# Sensor_Glove_ECG-X01.net
KiCad netlist of a schematic drawn in Altium Designer
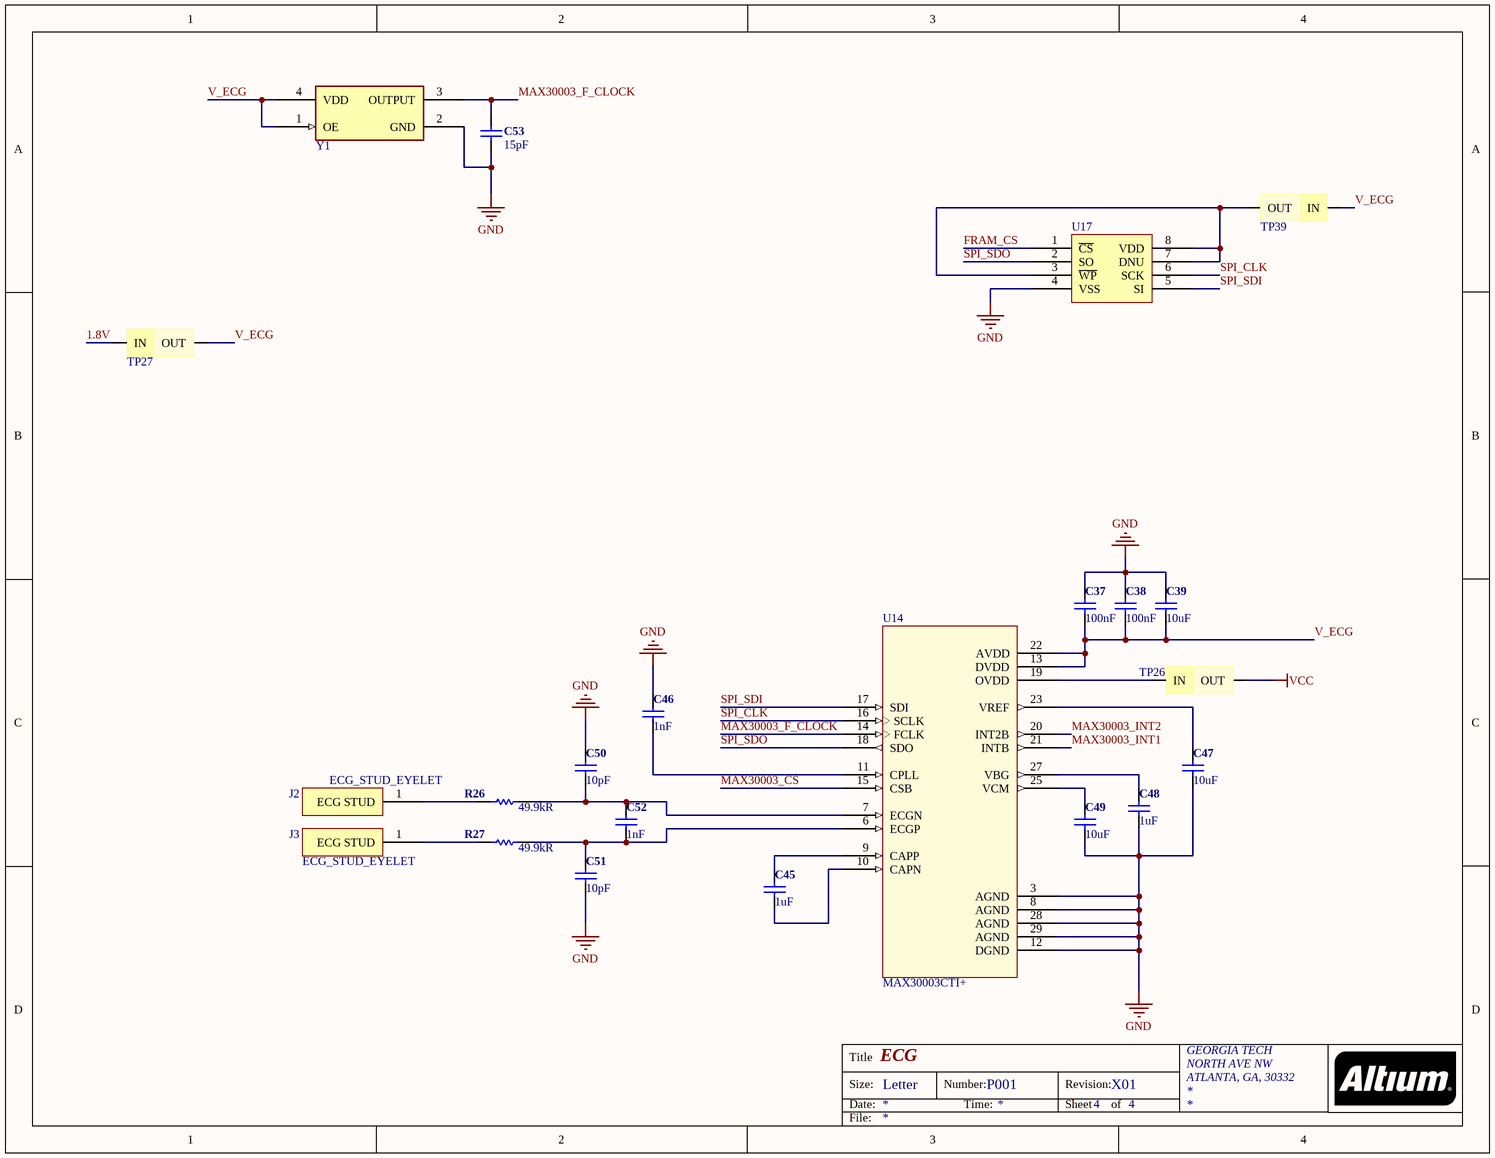
[diagram p0: Sensor_Glove_ECG-X01.SchDoc]

(export (version "E")
  (design (tool "Eeschema 10.0.6"))
  (components
    (comp (ref "C37")
      (value "100nF")
      (footprint "C0603")
      (fields
        (field (name "MANUFACTURER") "Yageo")
        (field (name "MANUFACTURER PART NUMBER") "CC0402ZRY5V8BB104")
        (field (name "TOLERANCE") "80%")
      )
      (libsource (lib "DB-X01") (part "C-0603(1608)"))
    )
    (comp (ref "C38")
      (value "100nF")
      (footprint "C0603")
      (fields
        (field (name "MANUFACTURER") "Yageo")
        (field (name "MANUFACTURER PART NUMBER") "CC0402ZRY5V8BB104")
        (field (name "TOLERANCE") "80%")
      )
      (libsource (lib "DB-X01") (part "C-0603(1608)"))
    )
    (comp (ref "C39")
      (value "10uF")
      (footprint "C0603")
      (fields
        (field (name "MANUFACTURER") "Murata")
        (field (name "MANUFACTURER PART NUMBER") "GRM188R61E106MA73J")
        (field (name "TOLERANCE") "20%")
      )
      (libsource (lib "DB-X01") (part "C-0603(1608)"))
    )
    (comp (ref "C45")
      (value "1uF")
      (footprint "C0402")
      (fields
        (field (name "MANUFACTURER") "Yageo")
        (field (name "MANUFACTURER PART NUMBER") "CC0402MRX5R5BB105")
        (field (name "TOLERANCE") "20%")
      )
      (libsource (lib "DB-X01") (part "C-0402(1005)"))
    )
    (comp (ref "C46")
      (value "1nF")
      (footprint "C0402")
      (description "Ceramic Capacitor, Multilayer, Ceramic, 10V, 5% +Tol, 5% -Tol, C0G, -/+30ppm/Cel TC, 0.001uF, 0402")
      (fields
        (field (name "MANUFACTURER") "KEMET")
        (field (name "MANUFACTURER PART NUMBER") "C0402C102J8GAC7867")
      )
      (libsource (lib "DB-X01") (part "C-0402(1005)"))
    )
    (comp (ref "C47")
      (value "10uF")
      (footprint "C0603")
      (fields
        (field (name "MANUFACTURER") "Murata")
        (field (name "MANUFACTURER PART NUMBER") "GRM188R61E106MA73J")
        (field (name "TOLERANCE") "20%")
      )
      (libsource (lib "DB-X01") (part "C-0603(1608)"))
    )
    (comp (ref "C48")
      (value "1uF")
      (footprint "C0402")
      (fields
        (field (name "MANUFACTURER") "Yageo")
        (field (name "MANUFACTURER PART NUMBER") "CC0402MRX5R5BB105")
        (field (name "TOLERANCE") "20%")
      )
      (libsource (lib "DB-X01") (part "C-0402(1005)"))
    )
    (comp (ref "C49")
      (value "10uF")
      (footprint "C0603")
      (fields
        (field (name "MANUFACTURER") "Murata")
        (field (name "MANUFACTURER PART NUMBER") "GRM188R61E106MA73J")
        (field (name "TOLERANCE") "20%")
      )
      (libsource (lib "DB-X01") (part "C-0603(1608)"))
    )
    (comp (ref "C50")
      (value "10pF")
      (footprint "C0402")
      (fields
        (field (name "MANUFACTURER") "Murata")
        (field (name "MANUFACTURER PART NUMBER") "GJM1555C1H100JB01D")
        (field (name "TOLERANCE") "5%")
      )
      (libsource (lib "DB-X01") (part "C-0402(1005)"))
    )
    (comp (ref "C51")
      (value "10pF")
      (footprint "C0402")
      (fields
        (field (name "MANUFACTURER") "Murata")
        (field (name "MANUFACTURER PART NUMBER") "GJM1555C1H100JB01D")
        (field (name "TOLERANCE") "5%")
      )
      (libsource (lib "DB-X01") (part "C-0402(1005)"))
    )
    (comp (ref "C52")
      (value "1nF")
      (footprint "C0402")
      (description "Ceramic Capacitor, Multilayer, Ceramic, 10V, 5% +Tol, 5% -Tol, C0G, -/+30ppm/Cel TC, 0.001uF, 0402")
      (fields
        (field (name "MANUFACTURER") "KEMET")
        (field (name "MANUFACTURER PART NUMBER") "C0402C102J8GAC7867")
      )
      (libsource (lib "DB-X01") (part "C-0402(1005)"))
    )
    (comp (ref "C53")
      (value "15pF")
      (footprint "C0402")
      (fields
        (field (name "MANUFACTURER") "Murata")
        (field (name "MANUFACTURER PART NUMBER") "GJM1555C1H150FB01D")
        (field (name "TOLERANCE") "1%")
      )
      (libsource (lib "DB-X02") (part "C-0402(1005)"))
    )
    (comp (ref "J2")
      (value "ECG_STUD_EYELET")
      (footprint "ECG_STUD")
      (libsource (lib "DB-X01") (part "ECG_STUD_EYELET"))
    )
    (comp (ref "J3")
      (value "ECG_STUD_EYELET")
      (footprint "ECG_STUD")
      (libsource (lib "DB-X01") (part "ECG_STUD_EYELET"))
    )
    (comp (ref "R26")
      (value "49.9kR")
      (footprint "R0402")
      (fields
        (field (name "MANUFACTURER") "Yageo")
        (field (name "MANUFACTURER PART NUMBER") "AC0402FR-0749K9L")
        (field (name "TOLERANCE") "1%")
      )
      (libsource (lib "DB-X01") (part "R-0402(1005)"))
    )
    (comp (ref "R27")
      (value "49.9kR")
      (footprint "R0402")
      (fields
        (field (name "MANUFACTURER") "Yageo")
        (field (name "MANUFACTURER PART NUMBER") "AC0402FR-0749K9L")
        (field (name "TOLERANCE") "1%")
      )
      (libsource (lib "DB-X01") (part "R-0402(1005)"))
    )
    (comp (ref "TP26")
      (value "JUMPER")
      (footprint "JUMPER")
      (description "SHUNT LP W/HANDLE 2 POS 30AU")
      (fields
        (field (name "MANUFACTURER") "TE Connectivity")
        (field (name "MANUFACTURER PART NUMBER") "8815452")
      )
      (libsource (lib "") (part "JUMPER_1"))
    )
    (comp (ref "TP27")
      (value "JUMPER")
      (footprint "JUMPER")
      (description "SHUNT LP W/HANDLE 2 POS 30AU")
      (fields
        (field (name "MANUFACTURER") "TE Connectivity")
        (field (name "MANUFACTURER PART NUMBER") "8815452")
      )
      (libsource (lib "") (part "JUMPER_1"))
    )
    (comp (ref "TP39")
      (value "JUMPER")
      (footprint "JUMPER")
      (description "SHUNT LP W/HANDLE 2 POS 30AU")
      (fields
        (field (name "MANUFACTURER") "TE Connectivity")
        (field (name "MANUFACTURER PART NUMBER") "8815452")
      )
      (libsource (lib "DB-X02") (part "JUMPER"))
    )
    (comp (ref "U14")
      (value "MAX30003CTI+")
      (footprint "QFN50P500X500X80-29N")
      (description "Analog Circuit, 1 Func, CMOS")
      (fields (field (name "MANUFACTURER") "Maxim"))
      (libsource (lib "DB-X01") (part "MAX30003CTI+"))
    )
    (comp (ref "U17")
      (value "8 MB FRAM")
      (footprint "GQFN-8")
      (description "Memory Circuit, 8 MB FRAM")
      (fields
        (field (name "MANUFACTURER") "Cypress")
        (field (name "MANUFACTURER PART NUMBER") "CY15B108QI-20LPXI")
      )
      (libsource (lib "DB-X02") (part "CY15B108QI"))
    )
    (comp (ref "Y1")
      (value "OSCILLATOR-32.768KHZ")
      (footprint "OSCILLATOR_4-SMD")
      (description "Oscillator Xo 0.032768MHZ ±25PPM 15PF Lvcmos/lvttl 55% 1.8V 4-PIN Csmd T/r")
      (fields
        (field (name "MANUFACTURER") "Diodes")
        (field (name "MANUFACTURER PART NUMBER") "KX2013B0032.768000")
      )
      (libsource (lib "DB-X02") (part "OSCILLATOR_32K768"))
    )
  )
  (nets
    (net (code "1") (name "/1.8V") (class "Default")
      (node (ref "TP27") (pin "1") (pinfunction "IN_1") (pintype "passive"))
    )
    (net (code "2") (name "/FRAM_CS") (class "Default")
      (node (ref "U17") (pin "1") (pinfunction "~{CS}_1") (pintype "passive"))
    )
    (net (code "3") (name "/MAX30003_CS") (class "Default")
      (node (ref "U14") (pin "15") (pinfunction "CSB_15") (pintype "input"))
    )
    (net (code "4") (name "/MAX30003_F_CLOCK") (class "Default")
      (node (ref "C53") (pin "1") (pinfunction "1_1") (pintype "passive"))
      (node (ref "U14") (pin "14") (pinfunction "FCLK_14") (pintype "input"))
      (node (ref "Y1") (pin "3") (pinfunction "OUTPUT_3") (pintype "passive"))
    )
    (net (code "5") (name "/MAX30003_INT1") (class "Default")
      (node (ref "U14") (pin "21") (pinfunction "INTB_21") (pintype "output"))
    )
    (net (code "6") (name "/MAX30003_INT2") (class "Default")
      (node (ref "U14") (pin "20") (pinfunction "INT2B_20") (pintype "output"))
    )
    (net (code "7") (name "/SPI_CLK") (class "Default")
      (node (ref "U14") (pin "16") (pinfunction "SCLK_16") (pintype "input"))
      (node (ref "U17") (pin "6") (pinfunction "SCK_6") (pintype "passive"))
    )
    (net (code "8") (name "/SPI_SDI") (class "Default")
      (node (ref "U14") (pin "17") (pinfunction "SDI_17") (pintype "input"))
      (node (ref "U17") (pin "5") (pinfunction "SI_5") (pintype "passive"))
    )
    (net (code "9") (name "/SPI_SDO") (class "Default")
      (node (ref "U14") (pin "18") (pinfunction "SDO_18") (pintype "output"))
      (node (ref "U17") (pin "2") (pinfunction "SO_2") (pintype "passive"))
    )
    (net (code "10") (name "/V_ECG") (class "Default")
      (node (ref "C37") (pin "1") (pinfunction "1_1") (pintype "passive"))
      (node (ref "C38") (pin "1") (pinfunction "1_1") (pintype "passive"))
      (node (ref "C39") (pin "1") (pinfunction "1_1") (pintype "passive"))
      (node (ref "TP27") (pin "2") (pinfunction "OUT_2") (pintype "passive"))
      (node (ref "TP39") (pin "1") (pinfunction "IN_1") (pintype "passive"))
      (node (ref "U14") (pin "13") (pinfunction "DVDD_13") (pintype "power_in"))
      (node (ref "U14") (pin "22") (pinfunction "AVDD_22") (pintype "power_in"))
      (node (ref "Y1") (pin "1") (pinfunction "OE_1") (pintype "input"))
      (node (ref "Y1") (pin "4") (pinfunction "VDD_4") (pintype "power_in"))
    )
    (net (code "11") (name "GND") (class "Default")
      (node (ref "C37") (pin "2") (pinfunction "2_2") (pintype "passive"))
      (node (ref "C38") (pin "2") (pinfunction "2_2") (pintype "passive"))
      (node (ref "C39") (pin "2") (pinfunction "2_2") (pintype "passive"))
      (node (ref "C46") (pin "1") (pinfunction "1_1") (pintype "passive"))
      (node (ref "C47") (pin "1") (pinfunction "1_1") (pintype "passive"))
      (node (ref "C48") (pin "2") (pinfunction "2_2") (pintype "passive"))
      (node (ref "C49") (pin "1") (pinfunction "1_1") (pintype "passive"))
      (node (ref "C50") (pin "1") (pinfunction "1_1") (pintype "passive"))
      (node (ref "C51") (pin "2") (pinfunction "2_2") (pintype "passive"))
      (node (ref "C53") (pin "2") (pinfunction "2_2") (pintype "passive"))
      (node (ref "U14") (pin "12") (pinfunction "DGND_12") (pintype "power_in"))
      (node (ref "U14") (pin "28") (pinfunction "AGND_28") (pintype "power_in"))
      (node (ref "U14") (pin "29") (pinfunction "AGND_29") (pintype "power_in"))
      (node (ref "U14") (pin "3") (pinfunction "AGND_3") (pintype "power_in"))
      (node (ref "U14") (pin "8") (pinfunction "AGND_8") (pintype "power_in"))
      (node (ref "U17") (pin "4") (pinfunction "VSS_4") (pintype "passive"))
      (node (ref "Y1") (pin "2") (pinfunction "GND_2") (pintype "power_in"))
    )
    (net (code "12") (name "Net-(J2-ECG_STUD)") (class "Default")
      (node (ref "J2") (pin "1") (pinfunction "ECG_STUD_1") (pintype "passive"))
      (node (ref "R26") (pin "1") (pinfunction "1_1") (pintype "passive"))
    )
    (net (code "13") (name "Net-(J3-ECG_STUD)") (class "Default")
      (node (ref "J3") (pin "1") (pinfunction "ECG_STUD_1") (pintype "passive"))
      (node (ref "R27") (pin "1") (pinfunction "1_1") (pintype "passive"))
    )
    (net (code "14") (name "Net-(TP26-IN)") (class "Default")
      (node (ref "TP26") (pin "1") (pinfunction "IN_1") (pintype "passive"))
      (node (ref "U14") (pin "19") (pinfunction "OVDD_19") (pintype "power_in"))
    )
    (net (code "15") (name "Net-(TP39-OUT)") (class "Default")
      (node (ref "TP39") (pin "2") (pinfunction "OUT_2") (pintype "passive"))
      (node (ref "U17") (pin "3") (pinfunction "~{WP}_3") (pintype "passive"))
      (node (ref "U17") (pin "7") (pinfunction "DNU_7") (pintype "passive"))
      (node (ref "U17") (pin "8") (pinfunction "VDD_8") (pintype "passive"))
    )
    (net (code "16") (name "Net-(U14-CAPN)") (class "Default")
      (node (ref "C45") (pin "2") (pinfunction "2_2") (pintype "passive"))
      (node (ref "U14") (pin "10") (pinfunction "CAPN_10") (pintype "input"))
    )
    (net (code "17") (name "Net-(U14-CAPP)") (class "Default")
      (node (ref "C45") (pin "1") (pinfunction "1_1") (pintype "passive"))
      (node (ref "U14") (pin "9") (pinfunction "CAPP_9") (pintype "input"))
    )
    (net (code "18") (name "Net-(U14-CPLL)") (class "Default")
      (node (ref "C46") (pin "2") (pinfunction "2_2") (pintype "passive"))
      (node (ref "U14") (pin "11") (pinfunction "CPLL_11") (pintype "input"))
    )
    (net (code "19") (name "Net-(U14-ECGN)") (class "Default")
      (node (ref "C50") (pin "2") (pinfunction "2_2") (pintype "passive"))
      (node (ref "C52") (pin "1") (pinfunction "1_1") (pintype "passive"))
      (node (ref "R26") (pin "2") (pinfunction "2_2") (pintype "passive"))
      (node (ref "U14") (pin "7") (pinfunction "ECGN_7") (pintype "input"))
    )
    (net (code "20") (name "Net-(U14-ECGP)") (class "Default")
      (node (ref "C51") (pin "1") (pinfunction "1_1") (pintype "passive"))
      (node (ref "C52") (pin "2") (pinfunction "2_2") (pintype "passive"))
      (node (ref "R27") (pin "2") (pinfunction "2_2") (pintype "passive"))
      (node (ref "U14") (pin "6") (pinfunction "ECGP_6") (pintype "input"))
    )
    (net (code "21") (name "Net-(U14-VBG)") (class "Default")
      (node (ref "C48") (pin "1") (pinfunction "1_1") (pintype "passive"))
      (node (ref "U14") (pin "27") (pinfunction "VBG_27") (pintype "output"))
    )
    (net (code "22") (name "Net-(U14-VCM)") (class "Default")
      (node (ref "C49") (pin "2") (pinfunction "2_2") (pintype "passive"))
      (node (ref "U14") (pin "25") (pinfunction "VCM_25") (pintype "output"))
    )
    (net (code "23") (name "Net-(U14-VREF)") (class "Default")
      (node (ref "C47") (pin "2") (pinfunction "2_2") (pintype "passive"))
      (node (ref "U14") (pin "23") (pinfunction "VREF_23") (pintype "output"))
    )
    (net (code "24") (name "VCC") (class "Default")
      (node (ref "TP26") (pin "2") (pinfunction "OUT_2") (pintype "passive"))
    )
  )
)
